# program.net
KiCad netlist of a schematic drawn in Altium Designer
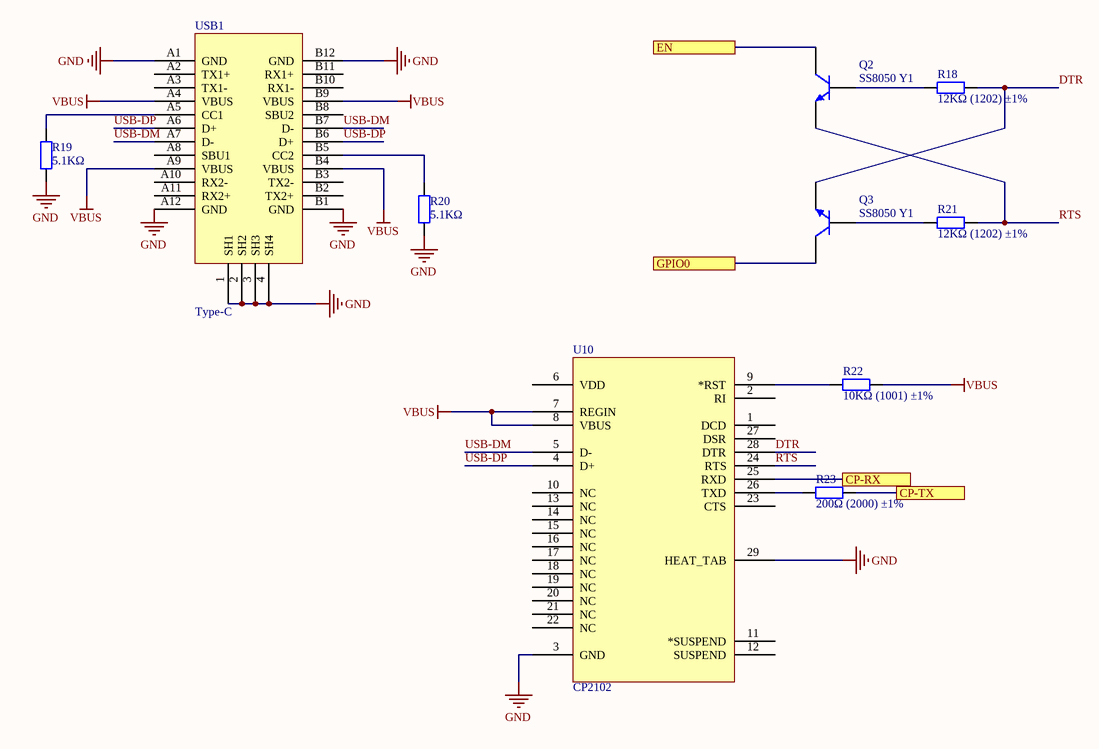
[diagram p0: program.SchDoc]

(export (version "E")
  (design (tool "Eeschema 10.0.6"))
  (components
    (comp (ref "Q2")
      (value "SS8050 Y1")
      (footprint "SOT-23(SOT-23-3)")
      (description "三极管")
      (libsource (lib "Miscellaneous Devices LC") (part "SOT-23 SS8050 Y1"))
    )
    (comp (ref "Q3")
      (value "SS8050 Y1")
      (footprint "SOT-23(SOT-23-3)")
      (description "三极管")
      (libsource (lib "Miscellaneous Devices LC") (part "SOT-23 SS8050 Y1"))
    )
    (comp (ref "R18")
      (value "12KΩ (1202) ±1%")
      (footprint "0402_R")
      (description "贴片电阻")
      (libsource (lib "Miscellaneous Devices LC") (part "0402 12KΩ (1202) 1%"))
    )
    (comp (ref "R19")
      (value "5.1KΩ")
      (footprint "0402_R")
      (description "贴片电阻")
      (libsource (lib "Miscellaneous Devices LC") (part "0402 5.1KΩ (5101) 1%"))
    )
    (comp (ref "R20")
      (value "5.1KΩ")
      (footprint "0402_R")
      (description "贴片电阻")
      (libsource (lib "Miscellaneous Devices LC") (part "0402 5.1KΩ (5101) 1%"))
    )
    (comp (ref "R21")
      (value "12KΩ (1202) ±1%")
      (footprint "0402_R")
      (description "贴片电阻")
      (libsource (lib "Miscellaneous Devices LC") (part "0402 12KΩ (1202) 1%"))
    )
    (comp (ref "R22")
      (value "10KΩ (1001) ±1%")
      (footprint "0402_R")
      (description "贴片电阻")
      (libsource (lib "Miscellaneous Devices LC") (part "0402 1KΩ (1001) 1%"))
    )
    (comp (ref "R23")
      (value "200Ω (2000) ±1%")
      (footprint "0402_R")
      (description "贴片电阻")
      (libsource (lib "Miscellaneous Devices LC") (part "0402 200Ω (2000) 1%"))
    )
    (comp (ref "U10")
      (value "CP2102")
      (footprint "QFN-28")
      (description "USB转TTL")
      (libsource (lib "M-WatchSchlib1") (part "CP2102"))
    )
    (comp (ref "USB1")
      (value "Type-C")
      (footprint "Type-C-TOP")
      (libsource (lib "M-WatchSchlib1") (part "USB-Type-C-TOP"))
    )
  )
  (nets
    (net (code "1") (name "/CP-RX") (class "Default")
      (node (ref "U10") (pin "25") (pinfunction "RXD_25") (pintype "passive"))
    )
    (net (code "2") (name "/CP-TX") (class "Default")
      (node (ref "R23") (pin "2") (pinfunction "2_2") (pintype "passive"))
    )
    (net (code "3") (name "/DTR") (class "Default")
      (node (ref "Q3") (pin "2") (pinfunction "E_2") (pintype "passive"))
      (node (ref "R18") (pin "2") (pinfunction "2_2") (pintype "passive"))
      (node (ref "U10") (pin "28") (pinfunction "DTR_28") (pintype "passive"))
    )
    (net (code "4") (name "/EN") (class "Default")
      (node (ref "Q2") (pin "3") (pinfunction "C_3") (pintype "passive"))
    )
    (net (code "5") (name "/GPIO0") (class "Default")
      (node (ref "Q3") (pin "3") (pinfunction "C_3") (pintype "passive"))
    )
    (net (code "6") (name "/RTS") (class "Default")
      (node (ref "Q2") (pin "2") (pinfunction "E_2") (pintype "passive"))
      (node (ref "R21") (pin "2") (pinfunction "2_2") (pintype "passive"))
      (node (ref "U10") (pin "24") (pinfunction "RTS_24") (pintype "passive"))
    )
    (net (code "7") (name "/USB-DM") (class "Default")
      (node (ref "U10") (pin "5") (pinfunction "D-_5") (pintype "passive"))
      (node (ref "USB1") (pin "A7") (pinfunction "D-_A7") (pintype "passive"))
      (node (ref "USB1") (pin "B7") (pinfunction "D-_B7") (pintype "passive"))
    )
    (net (code "8") (name "/USB-DP") (class "Default")
      (node (ref "U10") (pin "4") (pinfunction "D+_4") (pintype "passive"))
      (node (ref "USB1") (pin "A6") (pinfunction "D+_A6") (pintype "passive"))
      (node (ref "USB1") (pin "B6") (pinfunction "D+_B6") (pintype "passive"))
    )
    (net (code "9") (name "GND") (class "Default")
      (node (ref "R19") (pin "1") (pinfunction "1_1") (pintype "passive"))
      (node (ref "R20") (pin "1") (pinfunction "1_1") (pintype "passive"))
      (node (ref "U10") (pin "29") (pinfunction "HEAT_TAB_29") (pintype "passive"))
      (node (ref "U10") (pin "3") (pinfunction "GND_3") (pintype "passive"))
      (node (ref "USB1") (pin "1") (pinfunction "SH1_1") (pintype "passive"))
      (node (ref "USB1") (pin "2") (pinfunction "SH2_2") (pintype "passive"))
      (node (ref "USB1") (pin "3") (pinfunction "SH3_3") (pintype "passive"))
      (node (ref "USB1") (pin "4") (pinfunction "SH4_4") (pintype "passive"))
      (node (ref "USB1") (pin "A1") (pinfunction "GND_A1") (pintype "passive"))
      (node (ref "USB1") (pin "A12") (pinfunction "GND_A12") (pintype "passive"))
      (node (ref "USB1") (pin "B1") (pinfunction "GND_B1") (pintype "passive"))
      (node (ref "USB1") (pin "B12") (pinfunction "GND_B12") (pintype "passive"))
    )
    (net (code "10") (name "Net-(Q2-B)") (class "Default")
      (node (ref "Q2") (pin "1") (pinfunction "B_1") (pintype "passive"))
      (node (ref "R18") (pin "1") (pinfunction "1_1") (pintype "passive"))
    )
    (net (code "11") (name "Net-(Q3-B)") (class "Default")
      (node (ref "Q3") (pin "1") (pinfunction "B_1") (pintype "passive"))
      (node (ref "R21") (pin "1") (pinfunction "1_1") (pintype "passive"))
    )
    (net (code "12") (name "Net-(U10-*RST)") (class "Default")
      (node (ref "R22") (pin "1") (pinfunction "1_1") (pintype "passive"))
      (node (ref "U10") (pin "9") (pinfunction "*RST_9") (pintype "passive"))
    )
    (net (code "13") (name "Net-(U10-TXD)") (class "Default")
      (node (ref "R23") (pin "1") (pinfunction "1_1") (pintype "passive"))
      (node (ref "U10") (pin "26") (pinfunction "TXD_26") (pintype "passive"))
    )
    (net (code "14") (name "Net-(USB1-CC1)") (class "Default")
      (node (ref "R19") (pin "2") (pinfunction "2_2") (pintype "passive"))
      (node (ref "USB1") (pin "A5") (pinfunction "CC1_A5") (pintype "passive"))
    )
    (net (code "15") (name "Net-(USB1-CC2)") (class "Default")
      (node (ref "R20") (pin "2") (pinfunction "2_2") (pintype "passive"))
      (node (ref "USB1") (pin "B5") (pinfunction "CC2_B5") (pintype "passive"))
    )
    (net (code "16") (name "VBUS") (class "Default")
      (node (ref "R22") (pin "2") (pinfunction "2_2") (pintype "passive"))
      (node (ref "U10") (pin "7") (pinfunction "REGIN_7") (pintype "passive"))
      (node (ref "U10") (pin "8") (pinfunction "VBUS_8") (pintype "passive"))
      (node (ref "USB1") (pin "A4") (pinfunction "VBUS_A4") (pintype "passive"))
      (node (ref "USB1") (pin "A9") (pinfunction "VBUS_A9") (pintype "passive"))
      (node (ref "USB1") (pin "B4") (pinfunction "VBUS_B4") (pintype "passive"))
      (node (ref "USB1") (pin "B9") (pinfunction "VBUS_B9") (pintype "passive"))
    )
    (net (code "17") (name "unconnected-(U10-*SUSPEND-Pad11)") (class "Default")
      (node (ref "U10") (pin "11") (pinfunction "*SUSPEND_11") (pintype "passive"))
    )
    (net (code "18") (name "unconnected-(U10-CTS-Pad23)") (class "Default")
      (node (ref "U10") (pin "23") (pinfunction "CTS_23") (pintype "passive"))
    )
    (net (code "19") (name "unconnected-(U10-DCD-Pad1)") (class "Default")
      (node (ref "U10") (pin "1") (pinfunction "DCD_1") (pintype "passive"))
    )
    (net (code "20") (name "unconnected-(U10-DSR-Pad27)") (class "Default")
      (node (ref "U10") (pin "27") (pinfunction "DSR_27") (pintype "passive"))
    )
    (net (code "21") (name "unconnected-(U10-NC-Pad10)") (class "Default")
      (node (ref "U10") (pin "10") (pinfunction "NC_10") (pintype "passive"))
    )
    (net (code "22") (name "unconnected-(U10-NC-Pad13)") (class "Default")
      (node (ref "U10") (pin "13") (pinfunction "NC_13") (pintype "passive"))
    )
    (net (code "23") (name "unconnected-(U10-NC-Pad14)") (class "Default")
      (node (ref "U10") (pin "14") (pinfunction "NC_14") (pintype "passive"))
    )
    (net (code "24") (name "unconnected-(U10-NC-Pad15)") (class "Default")
      (node (ref "U10") (pin "15") (pinfunction "NC_15") (pintype "passive"))
    )
    (net (code "25") (name "unconnected-(U10-NC-Pad16)") (class "Default")
      (node (ref "U10") (pin "16") (pinfunction "NC_16") (pintype "passive"))
    )
    (net (code "26") (name "unconnected-(U10-NC-Pad17)") (class "Default")
      (node (ref "U10") (pin "17") (pinfunction "NC_17") (pintype "passive"))
    )
    (net (code "27") (name "unconnected-(U10-NC-Pad18)") (class "Default")
      (node (ref "U10") (pin "18") (pinfunction "NC_18") (pintype "passive"))
    )
    (net (code "28") (name "unconnected-(U10-NC-Pad19)") (class "Default")
      (node (ref "U10") (pin "19") (pinfunction "NC_19") (pintype "passive"))
    )
    (net (code "29") (name "unconnected-(U10-NC-Pad20)") (class "Default")
      (node (ref "U10") (pin "20") (pinfunction "NC_20") (pintype "passive"))
    )
    (net (code "30") (name "unconnected-(U10-NC-Pad21)") (class "Default")
      (node (ref "U10") (pin "21") (pinfunction "NC_21") (pintype "passive"))
    )
    (net (code "31") (name "unconnected-(U10-NC-Pad22)") (class "Default")
      (node (ref "U10") (pin "22") (pinfunction "NC_22") (pintype "passive"))
    )
    (net (code "32") (name "unconnected-(U10-RI-Pad2)") (class "Default")
      (node (ref "U10") (pin "2") (pinfunction "RI_2") (pintype "passive"))
    )
    (net (code "33") (name "unconnected-(U10-SUSPEND-Pad12)") (class "Default")
      (node (ref "U10") (pin "12") (pinfunction "SUSPEND_12") (pintype "passive"))
    )
    (net (code "34") (name "unconnected-(U10-VDD-Pad6)") (class "Default")
      (node (ref "U10") (pin "6") (pinfunction "VDD_6") (pintype "passive"))
    )
    (net (code "35") (name "unconnected-(USB1-RX1+-PadB11)") (class "Default")
      (node (ref "USB1") (pin "B11") (pinfunction "RX1+_B11") (pintype "passive"))
    )
    (net (code "36") (name "unconnected-(USB1-RX1--PadB10)") (class "Default")
      (node (ref "USB1") (pin "B10") (pinfunction "RX1-_B10") (pintype "passive"))
    )
    (net (code "37") (name "unconnected-(USB1-RX2+-PadA11)") (class "Default")
      (node (ref "USB1") (pin "A11") (pinfunction "RX2+_A11") (pintype "passive"))
    )
    (net (code "38") (name "unconnected-(USB1-RX2--PadA10)") (class "Default")
      (node (ref "USB1") (pin "A10") (pinfunction "RX2-_A10") (pintype "passive"))
    )
    (net (code "39") (name "unconnected-(USB1-SBU1-PadA8)") (class "Default")
      (node (ref "USB1") (pin "A8") (pinfunction "SBU1_A8") (pintype "passive"))
    )
    (net (code "40") (name "unconnected-(USB1-SBU2-PadB8)") (class "Default")
      (node (ref "USB1") (pin "B8") (pinfunction "SBU2_B8") (pintype "passive"))
    )
    (net (code "41") (name "unconnected-(USB1-TX1+-PadA2)") (class "Default")
      (node (ref "USB1") (pin "A2") (pinfunction "TX1+_A2") (pintype "passive"))
    )
    (net (code "42") (name "unconnected-(USB1-TX1--PadA3)") (class "Default")
      (node (ref "USB1") (pin "A3") (pinfunction "TX1-_A3") (pintype "passive"))
    )
    (net (code "43") (name "unconnected-(USB1-TX2+-PadB2)") (class "Default")
      (node (ref "USB1") (pin "B2") (pinfunction "TX2+_B2") (pintype "passive"))
    )
    (net (code "44") (name "unconnected-(USB1-TX2--PadB3)") (class "Default")
      (node (ref "USB1") (pin "B3") (pinfunction "TX2-_B3") (pintype "passive"))
    )
  )
)
